# CRAFT_Current_Sense_Circuit_AJefferson.net
KiCad netlist of a schematic drawn in Altium Designer
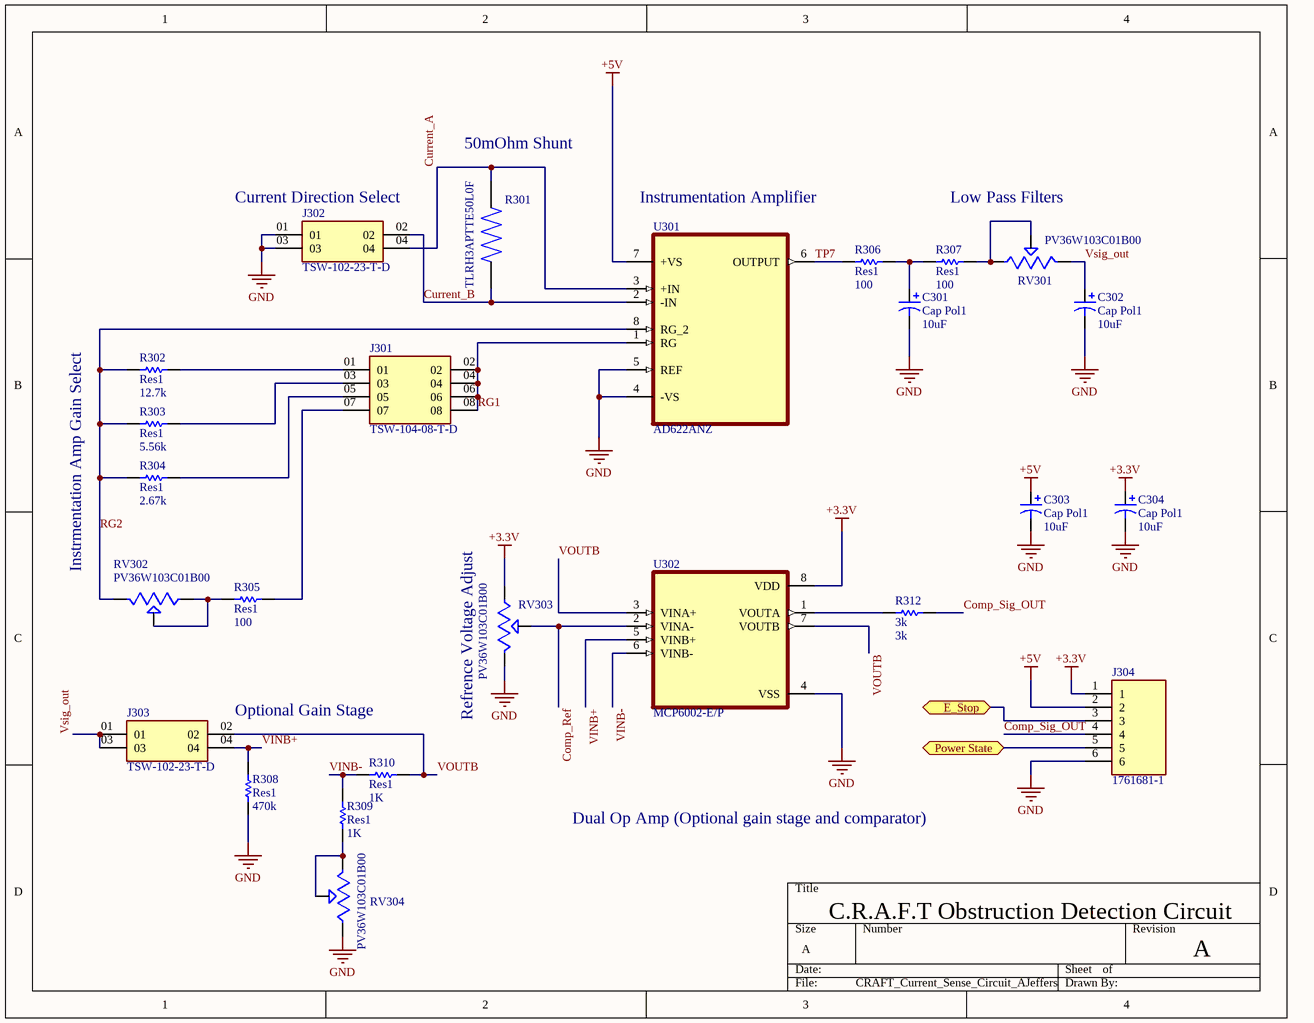
[diagram p0: CRAFT_Current_Sense_Circuit_AJefferson.SchDoc]

(export (version "E")
  (design (tool "Eeschema 10.0.6"))
  (components
    (comp (ref "C301")
      (value "Cap Pol1")
      (footprint "CAPPRD250W50D630H1120")
      (description "Polarized Capacitor (Radial)")
      (fields (field (name "ALTIUM_VALUE") "10uF") (field (name "PUBLISHER") "Altium Limited"))
      (libsource (lib "Miscellaneous Devices") (part "Cap Pol1"))
    )
    (comp (ref "C302")
      (value "Cap Pol1")
      (footprint "CAPPRD250W50D630H1120")
      (description "Polarized Capacitor (Radial)")
      (fields (field (name "ALTIUM_VALUE") "10uF") (field (name "PUBLISHER") "Altium Limited"))
      (libsource (lib "Miscellaneous Devices") (part "Cap Pol1"))
    )
    (comp (ref "C303")
      (value "Cap Pol1")
      (footprint "CAPPRD250W50D630H1120")
      (description "Polarized Capacitor (Radial)")
      (fields (field (name "ALTIUM_VALUE") "10uF") (field (name "PUBLISHER") "Altium Limited"))
      (libsource (lib "Miscellaneous Devices") (part "Cap Pol1"))
    )
    (comp (ref "C304")
      (value "Cap Pol1")
      (footprint "CAPPRD250W50D630H1120")
      (description "Polarized Capacitor (Radial)")
      (fields (field (name "ALTIUM_VALUE") "10uF") (field (name "PUBLISHER") "Altium Limited"))
      (libsource (lib "Miscellaneous Devices") (part "Cap Pol1"))
    )
    (comp (ref "J301")
      (value "TSW-104-08-T-D")
      (footprint "SAMTEC_TSW-104-08-T-D")
      (libsource (lib "TSW-104-08-T-D") (part "TSW-104-08-T-D"))
    )
    (comp (ref "J302")
      (value "TSW-102-23-T-D")
      (footprint "SAMTEC_TSW-102-23-T-D")
      (libsource (lib "TSW-102-23-T-D") (part "TSW-102-23-T-D"))
    )
    (comp (ref "J303")
      (value "TSW-102-23-T-D")
      (footprint "SAMTEC_TSW-102-23-T-D")
      (libsource (lib "TSW-102-23-T-D") (part "TSW-102-23-T-D"))
    )
    (comp (ref "J304")
      (value "1761681-1")
      (footprint "TE_1761681-1")
      (fields (field (name "MF") "{'manufacturer': 'TE Connectivity'}"))
      (libsource (lib "1761681-1") (part "1761681-1"))
    )
    (comp (ref "R301")
      (value "TLRH3APTTE50L0F")
      (footprint "RESC6332X70N")
      (description "Res Metal Plate 2512 0.047 Ohm 1% 4W Â±50ppm/C Pad SMD Automotive T/R")
      (fields (field (name "MP") "TLRH3APTTE47L0F"))
      (libsource (lib "TLRH3APTTE47L0F") (part "TLRH3APTTE47L0F"))
    )
    (comp (ref "R302")
      (value "Res1")
      (footprint "AXIAL-0.3")
      (description "Resistor")
      (fields (field (name "ALTIUM_VALUE") "12.7k") (field (name "PUBLISHER") "Altium Limited"))
      (libsource (lib "Miscellaneous Devices") (part "Res1"))
    )
    (comp (ref "R303")
      (value "Res1")
      (footprint "AXIAL-0.3")
      (description "Resistor")
      (fields (field (name "ALTIUM_VALUE") "5.56k") (field (name "PUBLISHER") "Altium Limited"))
      (libsource (lib "Miscellaneous Devices") (part "Res1"))
    )
    (comp (ref "R304")
      (value "Res1")
      (footprint "AXIAL-0.3")
      (description "Resistor")
      (fields (field (name "ALTIUM_VALUE") "2.67k") (field (name "PUBLISHER") "Altium Limited"))
      (libsource (lib "Miscellaneous Devices") (part "Res1"))
    )
    (comp (ref "R305")
      (value "Res1")
      (footprint "AXIAL-0.3")
      (description "Resistor")
      (fields (field (name "ALTIUM_VALUE") "100") (field (name "PUBLISHER") "Altium Limited"))
      (libsource (lib "Miscellaneous Devices") (part "Res1"))
    )
    (comp (ref "R306")
      (value "Res1")
      (footprint "AXIAL-0.3")
      (description "Resistor")
      (fields (field (name "ALTIUM_VALUE") "100") (field (name "PUBLISHER") "Altium Limited"))
      (libsource (lib "Miscellaneous Devices") (part "Res1"))
    )
    (comp (ref "R307")
      (value "Res1")
      (footprint "AXIAL-0.3")
      (description "Resistor")
      (fields (field (name "ALTIUM_VALUE") "100") (field (name "PUBLISHER") "Altium Limited"))
      (libsource (lib "Miscellaneous Devices") (part "Res1"))
    )
    (comp (ref "R308")
      (value "Res1")
      (footprint "AXIAL-0.3")
      (description "Resistor")
      (fields (field (name "ALTIUM_VALUE") "470k") (field (name "PUBLISHER") "Altium Limited"))
      (libsource (lib "Miscellaneous Devices") (part "Res1"))
    )
    (comp (ref "R309")
      (value "Res1")
      (footprint "AXIAL-0.3")
      (description "Resistor")
      (fields (field (name "ALTIUM_VALUE") "1K") (field (name "PUBLISHER") "Altium Limited"))
      (libsource (lib "Miscellaneous Devices") (part "Res1"))
    )
    (comp (ref "R310")
      (value "Res1")
      (footprint "AXIAL-0.3")
      (description "Resistor")
      (fields (field (name "ALTIUM_VALUE") "1K") (field (name "PUBLISHER") "Altium Limited"))
      (libsource (lib "Miscellaneous Devices") (part "Res1"))
    )
    (comp (ref "R312")
      (value "3k")
      (footprint "AXIAL-0.3")
      (description "Resistor")
      (fields (field (name "ALTIUM_VALUE") "3k") (field (name "PUBLISHER") "Altium Limited"))
      (libsource (lib "Miscellaneous Devices") (part "Res1"))
    )
    (comp (ref "RV301")
      (value "PV36W103C01B00")
      (footprint "TRIM_PV36W103C01B00")
      (description "10 kOhms 0.5W, 1/2W PC Pins Through Hole Trimmer Potentiometer Cermet 25 Turn Top Adjustment")
      (fields (field (name "MF") "Bourns"))
      (libsource (lib "PV36W103C01B00") (part "PV36W103C01B00"))
    )
    (comp (ref "RV302")
      (value "PV36W103C01B00")
      (footprint "TRIM_PV36W103C01B00")
      (description "10 kOhms 0.5W, 1/2W PC Pins Through Hole Trimmer Potentiometer Cermet 25 Turn Top Adjustment")
      (fields (field (name "MF") "Bourns"))
      (libsource (lib "PV36W103C01B00") (part "PV36W103C01B00"))
    )
    (comp (ref "RV303")
      (value "PV36W103C01B00")
      (footprint "TRIM_PV36W103C01B00")
      (description "10 kOhms 0.5W, 1/2W PC Pins Through Hole Trimmer Potentiometer Cermet 25 Turn Top Adjustment")
      (fields (field (name "MF") "Bourns"))
      (libsource (lib "PV36W103C01B00") (part "PV36W103C01B00"))
    )
    (comp (ref "RV304")
      (value "PV36W103C01B00")
      (footprint "TRIM_PV36W103C01B00")
      (description "10 kOhms 0.5W, 1/2W PC Pins Through Hole Trimmer Potentiometer Cermet 25 Turn Top Adjustment")
      (fields (field (name "MF") "Bourns"))
      (libsource (lib "PV36W103C01B00") (part "PV36W103C01B00"))
    )
    (comp (ref "U301")
      (value "AD622ANZ")
      (footprint "DIP254P762X533-8")
      (description "Instrumentation Amplifier 1 Circuit 8-PDIP")
      (fields (field (name "MF") "Analog Devices"))
      (libsource (lib "AD622ANZ") (part "AD622ANZ"))
    )
    (comp (ref "U302")
      (value "MCP6002-E/P")
      (footprint "DIP787W46P254L927H533Q8")
      (description "General Purpose Amplifier 2 Circuit Rail-to-Rail 8-PDIP")
      (fields (field (name "MF") "Microchip"))
      (libsource (lib "MCP6002-E_P") (part "MCP6002-E/P"))
    )
  )
  (nets
    (net (code "1") (name "+3.3V") (class "Default")
      (node (ref "C304") (pin "1") (pinfunction "1_1") (pintype "passive"))
      (node (ref "J304") (pin "1") (pinfunction "1_1") (pintype "passive"))
      (node (ref "RV303") (pin "1") (pinfunction "1_1") (pintype "passive"))
      (node (ref "U302") (pin "8") (pinfunction "VDD_8") (pintype "power_in"))
    )
    (net (code "2") (name "+5V") (class "Default")
      (node (ref "C303") (pin "1") (pinfunction "1_1") (pintype "passive"))
      (node (ref "J304") (pin "2") (pinfunction "2_2") (pintype "passive"))
      (node (ref "U301") (pin "7") (pinfunction "+VS_7") (pintype "power_in"))
    )
    (net (code "3") (name "/Comp_Ref") (class "Default")
      (node (ref "RV303") (pin "2") (pinfunction "2_2") (pintype "passive"))
      (node (ref "U302") (pin "2") (pinfunction "VINA-_2") (pintype "input"))
    )
    (net (code "4") (name "/Comp_Sig_OUT") (class "Default")
      (node (ref "J304") (pin "4") (pinfunction "4_4") (pintype "passive"))
      (node (ref "R312") (pin "2") (pinfunction "2_2") (pintype "passive"))
    )
    (net (code "5") (name "/Current_A") (class "Default")
      (node (ref "J302") (pin "04") (pinfunction "04_04") (pintype "passive"))
      (node (ref "R301") (pin "2") (pinfunction "2_2") (pintype "passive"))
      (node (ref "U301") (pin "3") (pinfunction "+IN_3") (pintype "input"))
    )
    (net (code "6") (name "/Current_B") (class "Default")
      (node (ref "J302") (pin "02") (pinfunction "02_02") (pintype "passive"))
      (node (ref "R301") (pin "1") (pinfunction "1_1") (pintype "passive"))
      (node (ref "U301") (pin "2") (pinfunction "-IN_2") (pintype "input"))
    )
    (net (code "7") (name "/E_Stop") (class "Default")
      (node (ref "J304") (pin "3") (pinfunction "3_3") (pintype "passive"))
    )
    (net (code "8") (name "/Power State") (class "Default")
      (node (ref "J304") (pin "5") (pinfunction "5_5") (pintype "passive"))
    )
    (net (code "9") (name "/RG1") (class "Default")
      (node (ref "J301") (pin "02") (pinfunction "02_02") (pintype "passive"))
      (node (ref "J301") (pin "04") (pinfunction "04_04") (pintype "passive"))
      (node (ref "J301") (pin "06") (pinfunction "06_06") (pintype "passive"))
      (node (ref "J301") (pin "08") (pinfunction "08_08") (pintype "passive"))
      (node (ref "U301") (pin "1") (pinfunction "RG_1") (pintype "input"))
    )
    (net (code "10") (name "/RG2") (class "Default")
      (node (ref "R302") (pin "1") (pinfunction "1_1") (pintype "passive"))
      (node (ref "R303") (pin "1") (pinfunction "1_1") (pintype "passive"))
      (node (ref "R304") (pin "1") (pinfunction "1_1") (pintype "passive"))
      (node (ref "RV302") (pin "3") (pinfunction "3_3") (pintype "passive"))
      (node (ref "U301") (pin "8") (pinfunction "RG_2_8") (pintype "input"))
    )
    (net (code "11") (name "/TP7") (class "Default")
      (node (ref "R306") (pin "1") (pinfunction "1_1") (pintype "passive"))
      (node (ref "U301") (pin "6") (pinfunction "OUTPUT_6") (pintype "output"))
    )
    (net (code "12") (name "/VINB+") (class "Default")
      (node (ref "J303") (pin "04") (pinfunction "04_04") (pintype "passive"))
      (node (ref "R308") (pin "2") (pinfunction "2_2") (pintype "passive"))
      (node (ref "U302") (pin "5") (pinfunction "VINB+_5") (pintype "input"))
    )
    (net (code "13") (name "/VINB-") (class "Default")
      (node (ref "R309") (pin "2") (pinfunction "2_2") (pintype "passive"))
      (node (ref "R310") (pin "1") (pinfunction "1_1") (pintype "passive"))
      (node (ref "U302") (pin "6") (pinfunction "VINB-_6") (pintype "input"))
    )
    (net (code "14") (name "/VOUTB") (class "Default")
      (node (ref "J303") (pin "02") (pinfunction "02_02") (pintype "passive"))
      (node (ref "R310") (pin "2") (pinfunction "2_2") (pintype "passive"))
      (node (ref "U302") (pin "3") (pinfunction "VINA+_3") (pintype "input"))
      (node (ref "U302") (pin "7") (pinfunction "VOUTB_7") (pintype "output"))
    )
    (net (code "15") (name "/Vsig_out") (class "Default")
      (node (ref "C302") (pin "1") (pinfunction "1_1") (pintype "passive"))
      (node (ref "J303") (pin "01") (pinfunction "01_01") (pintype "passive"))
      (node (ref "J303") (pin "03") (pinfunction "03_03") (pintype "passive"))
      (node (ref "RV301") (pin "3") (pinfunction "3_3") (pintype "passive"))
    )
    (net (code "16") (name "GND") (class "Default")
      (node (ref "C301") (pin "2") (pinfunction "2_2") (pintype "passive"))
      (node (ref "C302") (pin "2") (pinfunction "2_2") (pintype "passive"))
      (node (ref "C303") (pin "2") (pinfunction "2_2") (pintype "passive"))
      (node (ref "C304") (pin "2") (pinfunction "2_2") (pintype "passive"))
      (node (ref "J302") (pin "01") (pinfunction "01_01") (pintype "passive"))
      (node (ref "J302") (pin "03") (pinfunction "03_03") (pintype "passive"))
      (node (ref "J304") (pin "6") (pinfunction "6_6") (pintype "passive"))
      (node (ref "R308") (pin "1") (pinfunction "1_1") (pintype "passive"))
      (node (ref "RV303") (pin "3") (pinfunction "3_3") (pintype "passive"))
      (node (ref "RV304") (pin "1") (pinfunction "1_1") (pintype "passive"))
      (node (ref "U301") (pin "4") (pinfunction "-VS_4") (pintype "power_in"))
      (node (ref "U301") (pin "5") (pinfunction "REF_5") (pintype "input"))
      (node (ref "U302") (pin "4") (pinfunction "VSS_4") (pintype "power_in"))
    )
    (net (code "17") (name "Net-(C301-Pad1)") (class "Default")
      (node (ref "C301") (pin "1") (pinfunction "1_1") (pintype "passive"))
      (node (ref "R306") (pin "2") (pinfunction "2_2") (pintype "passive"))
      (node (ref "R307") (pin "1") (pinfunction "1_1") (pintype "passive"))
    )
    (net (code "18") (name "Net-(J301-Pad01)") (class "Default")
      (node (ref "J301") (pin "01") (pinfunction "01_01") (pintype "passive"))
      (node (ref "R302") (pin "2") (pinfunction "2_2") (pintype "passive"))
    )
    (net (code "19") (name "Net-(J301-Pad03)") (class "Default")
      (node (ref "J301") (pin "03") (pinfunction "03_03") (pintype "passive"))
      (node (ref "R303") (pin "2") (pinfunction "2_2") (pintype "passive"))
    )
    (net (code "20") (name "Net-(J301-Pad05)") (class "Default")
      (node (ref "J301") (pin "05") (pinfunction "05_05") (pintype "passive"))
      (node (ref "R304") (pin "2") (pinfunction "2_2") (pintype "passive"))
    )
    (net (code "21") (name "Net-(J301-Pad07)") (class "Default")
      (node (ref "J301") (pin "07") (pinfunction "07_07") (pintype "passive"))
      (node (ref "R305") (pin "2") (pinfunction "2_2") (pintype "passive"))
    )
    (net (code "22") (name "Net-(R305-Pad1)") (class "Default")
      (node (ref "R305") (pin "1") (pinfunction "1_1") (pintype "passive"))
      (node (ref "RV302") (pin "1") (pinfunction "1_1") (pintype "passive"))
      (node (ref "RV302") (pin "2") (pinfunction "2_2") (pintype "passive"))
    )
    (net (code "23") (name "Net-(R307-Pad2)") (class "Default")
      (node (ref "R307") (pin "2") (pinfunction "2_2") (pintype "passive"))
      (node (ref "RV301") (pin "1") (pinfunction "1_1") (pintype "passive"))
      (node (ref "RV301") (pin "2") (pinfunction "2_2") (pintype "passive"))
    )
    (net (code "24") (name "Net-(R309-Pad1)") (class "Default")
      (node (ref "R309") (pin "1") (pinfunction "1_1") (pintype "passive"))
      (node (ref "RV304") (pin "2") (pinfunction "2_2") (pintype "passive"))
      (node (ref "RV304") (pin "3") (pinfunction "3_3") (pintype "passive"))
    )
    (net (code "25") (name "Net-(U302-VOUTA)") (class "Default")
      (node (ref "R312") (pin "1") (pinfunction "1_1") (pintype "passive"))
      (node (ref "U302") (pin "1") (pinfunction "VOUTA_1") (pintype "output"))
    )
  )
)
